# Nusbio_smd.net
KiCad netlist of a schematic drawn in EAGLE
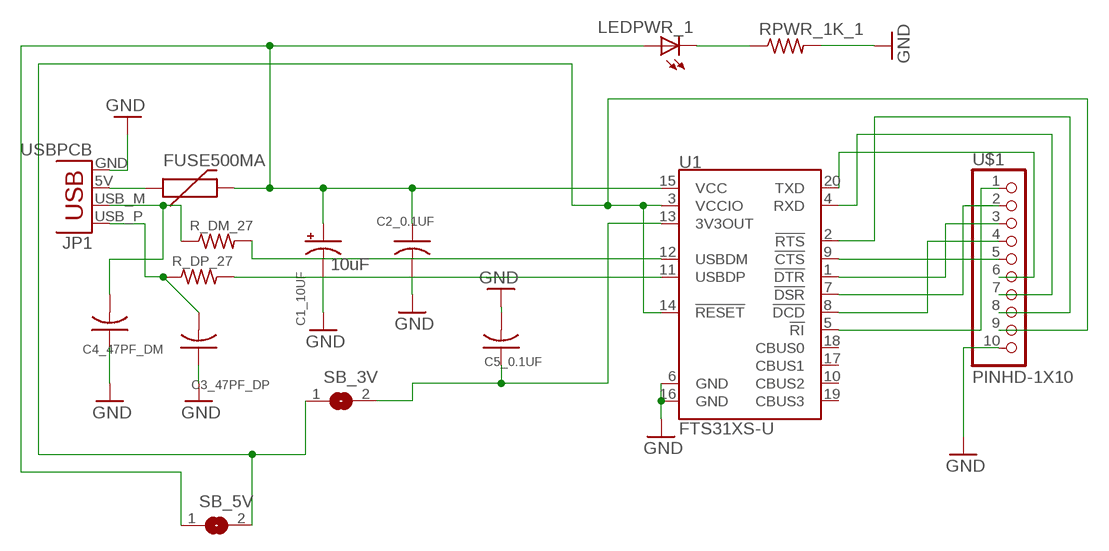
[diagram p0: schematic, sheet 1]

(export (version "E")
  (design (tool "Eeschema 10.0.6"))
  (components
    (comp (ref "C1_10UF")
      (value "10uF")
      (footprint "eagle-import:EIA3216")
      (libsource (lib "eagle-import") (part "10UF-16V-10%(TANT)"))
    )
    (comp (ref "C2_0.1UF")
      (value "C-USC1206")
      (footprint "eagle-import:C1206")
      (libsource (lib "eagle-import") (part "C-USC1206"))
    )
    (comp (ref "C3_47PF_DP")
      (value "C-USC1206")
      (footprint "eagle-import:C1206")
      (libsource (lib "eagle-import") (part "C-USC1206"))
    )
    (comp (ref "C4_47PF_DM")
      (value "C-USC1206")
      (footprint "eagle-import:C1206")
      (libsource (lib "eagle-import") (part "C-USC1206"))
    )
    (comp (ref "C5_0.1UF")
      (value "C-USC1206")
      (footprint "eagle-import:C1206")
      (libsource (lib "eagle-import") (part "C-USC1206"))
    )
    (comp (ref "FUSE500MA")
      (value "PTCSMD")
      (footprint "eagle-import:PTC-1206")
      (libsource (lib "eagle-import") (part "PTCSMD"))
    )
    (comp (ref "JP1")
      (value "USBPCB")
      (footprint "eagle-import:USB-A-PCB")
      (libsource (lib "eagle-import") (part "USBPCB"))
    )
    (comp (ref "LEDPWR_1")
      (value "LEDCHIPLED_0805")
      (footprint "eagle-import:CHIPLED_0805")
      (libsource (lib "eagle-import") (part "LEDCHIPLED_0805"))
    )
    (comp (ref "RPWR_1K_1")
      (value "R-US_R0805")
      (footprint "eagle-import:R0805")
      (libsource (lib "eagle-import") (part "R-US_R0805"))
    )
    (comp (ref "R_DM_27")
      (value "R-US_R0805")
      (footprint "eagle-import:R0805")
      (libsource (lib "eagle-import") (part "R-US_R0805"))
    )
    (comp (ref "R_DP_27")
      (value "R-US_R0805")
      (footprint "eagle-import:R0805")
      (libsource (lib "eagle-import") (part "R-US_R0805"))
    )
    (comp (ref "SB_3V")
      (value "SOLDERJUMPERREFLOW")
      (footprint "eagle-import:SOLDERJUMPER_REFLOW")
      (libsource (lib "eagle-import") (part "SOLDERJUMPERREFLOW"))
    )
    (comp (ref "SB_5V")
      (value "SOLDERJUMPERREFLOW")
      (footprint "eagle-import:SOLDERJUMPER_REFLOW")
      (libsource (lib "eagle-import") (part "SOLDERJUMPERREFLOW"))
    )
    (comp (ref "U$1")
      (value "PINHD-1X10")
      (footprint "eagle-import:1X10-BIG")
      (libsource (lib "eagle-import") (part "PINHD-1X10"))
    )
    (comp (ref "U1")
      (value "FTS31XS-U")
      (footprint "eagle-import:SSOP20_L")
      (libsource (lib "eagle-import") (part "FT231XS"))
    )
  )
  (nets
    (net (code "1") (name "GND") (class "Default")
      (node (ref "C1_10UF") (pin "C") (pinfunction "-_C") (pintype "passive"))
      (node (ref "C2_0.1UF") (pin "2") (pinfunction "2_2") (pintype "passive"))
      (node (ref "C3_47PF_DP") (pin "1") (pinfunction "1_1") (pintype "passive"))
      (node (ref "C4_47PF_DM") (pin "1") (pinfunction "1_1") (pintype "passive"))
      (node (ref "C5_0.1UF") (pin "2") (pinfunction "2_2") (pintype "passive"))
      (node (ref "JP1") (pin "GND") (pinfunction "GND_GND") (pintype "bidirectional"))
      (node (ref "RPWR_1K_1") (pin "2") (pinfunction "2_2") (pintype "passive"))
      (node (ref "U$1") (pin "10") (pinfunction "10_10") (pintype "passive"))
      (node (ref "U1") (pin "16") (pinfunction "GND_16") (pintype "bidirectional"))
      (node (ref "U1") (pin "6") (pinfunction "GND_6") (pintype "bidirectional"))
    )
    (net (code "2") (name "Net-(C1_10UF-+)") (class "Default")
      (node (ref "C1_10UF") (pin "A") (pinfunction "+_A") (pintype "passive"))
      (node (ref "C2_0.1UF") (pin "1") (pinfunction "1_1") (pintype "passive"))
      (node (ref "FUSE500MA") (pin "2") (pinfunction "2_2") (pintype "bidirectional"))
      (node (ref "LEDPWR_1") (pin "A") (pinfunction "A_A") (pintype "passive"))
      (node (ref "SB_5V") (pin "1") (pinfunction "1_1") (pintype "passive"))
      (node (ref "U1") (pin "15") (pinfunction "VCC_15") (pintype "bidirectional"))
    )
    (net (code "3") (name "Net-(JP1-D+)") (class "Default")
      (node (ref "C3_47PF_DP") (pin "2") (pinfunction "2_2") (pintype "passive"))
      (node (ref "JP1") (pin "USB_P") (pinfunction "D+_USB_P") (pintype "bidirectional"))
      (node (ref "R_DP_27") (pin "1") (pinfunction "1_1") (pintype "passive"))
    )
    (net (code "4") (name "Net-(JP1-D-)") (class "Default")
      (node (ref "C4_47PF_DM") (pin "2") (pinfunction "2_2") (pintype "passive"))
      (node (ref "JP1") (pin "USB_M") (pinfunction "D-_USB_M") (pintype "bidirectional"))
      (node (ref "R_DM_27") (pin "1") (pinfunction "1_1") (pintype "passive"))
    )
    (net (code "5") (name "Net-(JP1-VBUS)") (class "Default")
      (node (ref "FUSE500MA") (pin "1") (pinfunction "1_1") (pintype "bidirectional"))
      (node (ref "JP1") (pin "5V") (pinfunction "VBUS_5V") (pintype "bidirectional"))
    )
    (net (code "6") (name "Net-(LEDPWR_1-PadC)") (class "Default")
      (node (ref "LEDPWR_1") (pin "C") (pinfunction "C_C") (pintype "passive"))
      (node (ref "RPWR_1K_1") (pin "1") (pinfunction "1_1") (pintype "passive"))
    )
    (net (code "7") (name "Net-(U1-3V3OUT)") (class "Default")
      (node (ref "C5_0.1UF") (pin "1") (pinfunction "1_1") (pintype "passive"))
      (node (ref "SB_3V") (pin "2") (pinfunction "2_2") (pintype "passive"))
      (node (ref "U1") (pin "13") (pinfunction "3V3OUT_13") (pintype "bidirectional"))
    )
    (net (code "8") (name "Net-(U1-RXD)") (class "Default")
      (node (ref "U$1") (pin "7") (pinfunction "7_7") (pintype "passive"))
      (node (ref "U1") (pin "4") (pinfunction "RXD_4") (pintype "bidirectional"))
    )
    (net (code "9") (name "Net-(U1-TXD)") (class "Default")
      (node (ref "U$1") (pin "6") (pinfunction "6_6") (pintype "passive"))
      (node (ref "U1") (pin "20") (pinfunction "TXD_20") (pintype "bidirectional"))
    )
    (net (code "10") (name "Net-(U1-USBDM)") (class "Default")
      (node (ref "R_DM_27") (pin "2") (pinfunction "2_2") (pintype "passive"))
      (node (ref "U1") (pin "12") (pinfunction "USBDM_12") (pintype "bidirectional"))
    )
    (net (code "11") (name "Net-(U1-USBDP)") (class "Default")
      (node (ref "R_DP_27") (pin "2") (pinfunction "2_2") (pintype "passive"))
      (node (ref "U1") (pin "11") (pinfunction "USBDP_11") (pintype "bidirectional"))
    )
    (net (code "12") (name "Net-(U1-VCCIO)") (class "Default")
      (node (ref "SB_3V") (pin "1") (pinfunction "1_1") (pintype "passive"))
      (node (ref "SB_5V") (pin "2") (pinfunction "2_2") (pintype "passive"))
      (node (ref "U$1") (pin "9") (pinfunction "9_9") (pintype "passive"))
      (node (ref "U1") (pin "14") (pinfunction "~{RESET}_14") (pintype "bidirectional"))
      (node (ref "U1") (pin "3") (pinfunction "VCCIO_3") (pintype "bidirectional"))
    )
    (net (code "13") (name "Net-(U1-~{CTS})") (class "Default")
      (node (ref "U$1") (pin "5") (pinfunction "5_5") (pintype "passive"))
      (node (ref "U1") (pin "9") (pinfunction "~{CTS}_9") (pintype "bidirectional"))
    )
    (net (code "14") (name "Net-(U1-~{DCD})") (class "Default")
      (node (ref "U$1") (pin "4") (pinfunction "4_4") (pintype "passive"))
      (node (ref "U1") (pin "8") (pinfunction "~{DCD}_8") (pintype "bidirectional"))
    )
    (net (code "15") (name "Net-(U1-~{DSR})") (class "Default")
      (node (ref "U$1") (pin "2") (pinfunction "2_2") (pintype "passive"))
      (node (ref "U1") (pin "7") (pinfunction "~{DSR}_7") (pintype "bidirectional"))
    )
    (net (code "16") (name "Net-(U1-~{DTR})") (class "Default")
      (node (ref "U$1") (pin "3") (pinfunction "3_3") (pintype "passive"))
      (node (ref "U1") (pin "1") (pinfunction "~{DTR}_1") (pintype "bidirectional"))
    )
    (net (code "17") (name "Net-(U1-~{RI})") (class "Default")
      (node (ref "U$1") (pin "1") (pinfunction "1_1") (pintype "passive"))
      (node (ref "U1") (pin "5") (pinfunction "~{RI}_5") (pintype "bidirectional"))
    )
    (net (code "18") (name "Net-(U1-~{RTS})") (class "Default")
      (node (ref "U$1") (pin "8") (pinfunction "8_8") (pintype "passive"))
      (node (ref "U1") (pin "2") (pinfunction "~{RTS}_2") (pintype "bidirectional"))
    )
    (net (code "19") (name "unconnected-(U1-CBUS0-Pad18)") (class "Default")
      (node (ref "U1") (pin "18") (pinfunction "CBUS0_18") (pintype "bidirectional"))
    )
    (net (code "20") (name "unconnected-(U1-CBUS1-Pad17)") (class "Default")
      (node (ref "U1") (pin "17") (pinfunction "CBUS1_17") (pintype "bidirectional"))
    )
    (net (code "21") (name "unconnected-(U1-CBUS2-Pad10)") (class "Default")
      (node (ref "U1") (pin "10") (pinfunction "CBUS2_10") (pintype "bidirectional"))
    )
    (net (code "22") (name "unconnected-(U1-CBUS3-Pad19)") (class "Default")
      (node (ref "U1") (pin "19") (pinfunction "CBUS3_19") (pintype "bidirectional"))
    )
  )
)
